# 4-IO.net
KiCad netlist of a schematic drawn in Altium Designer
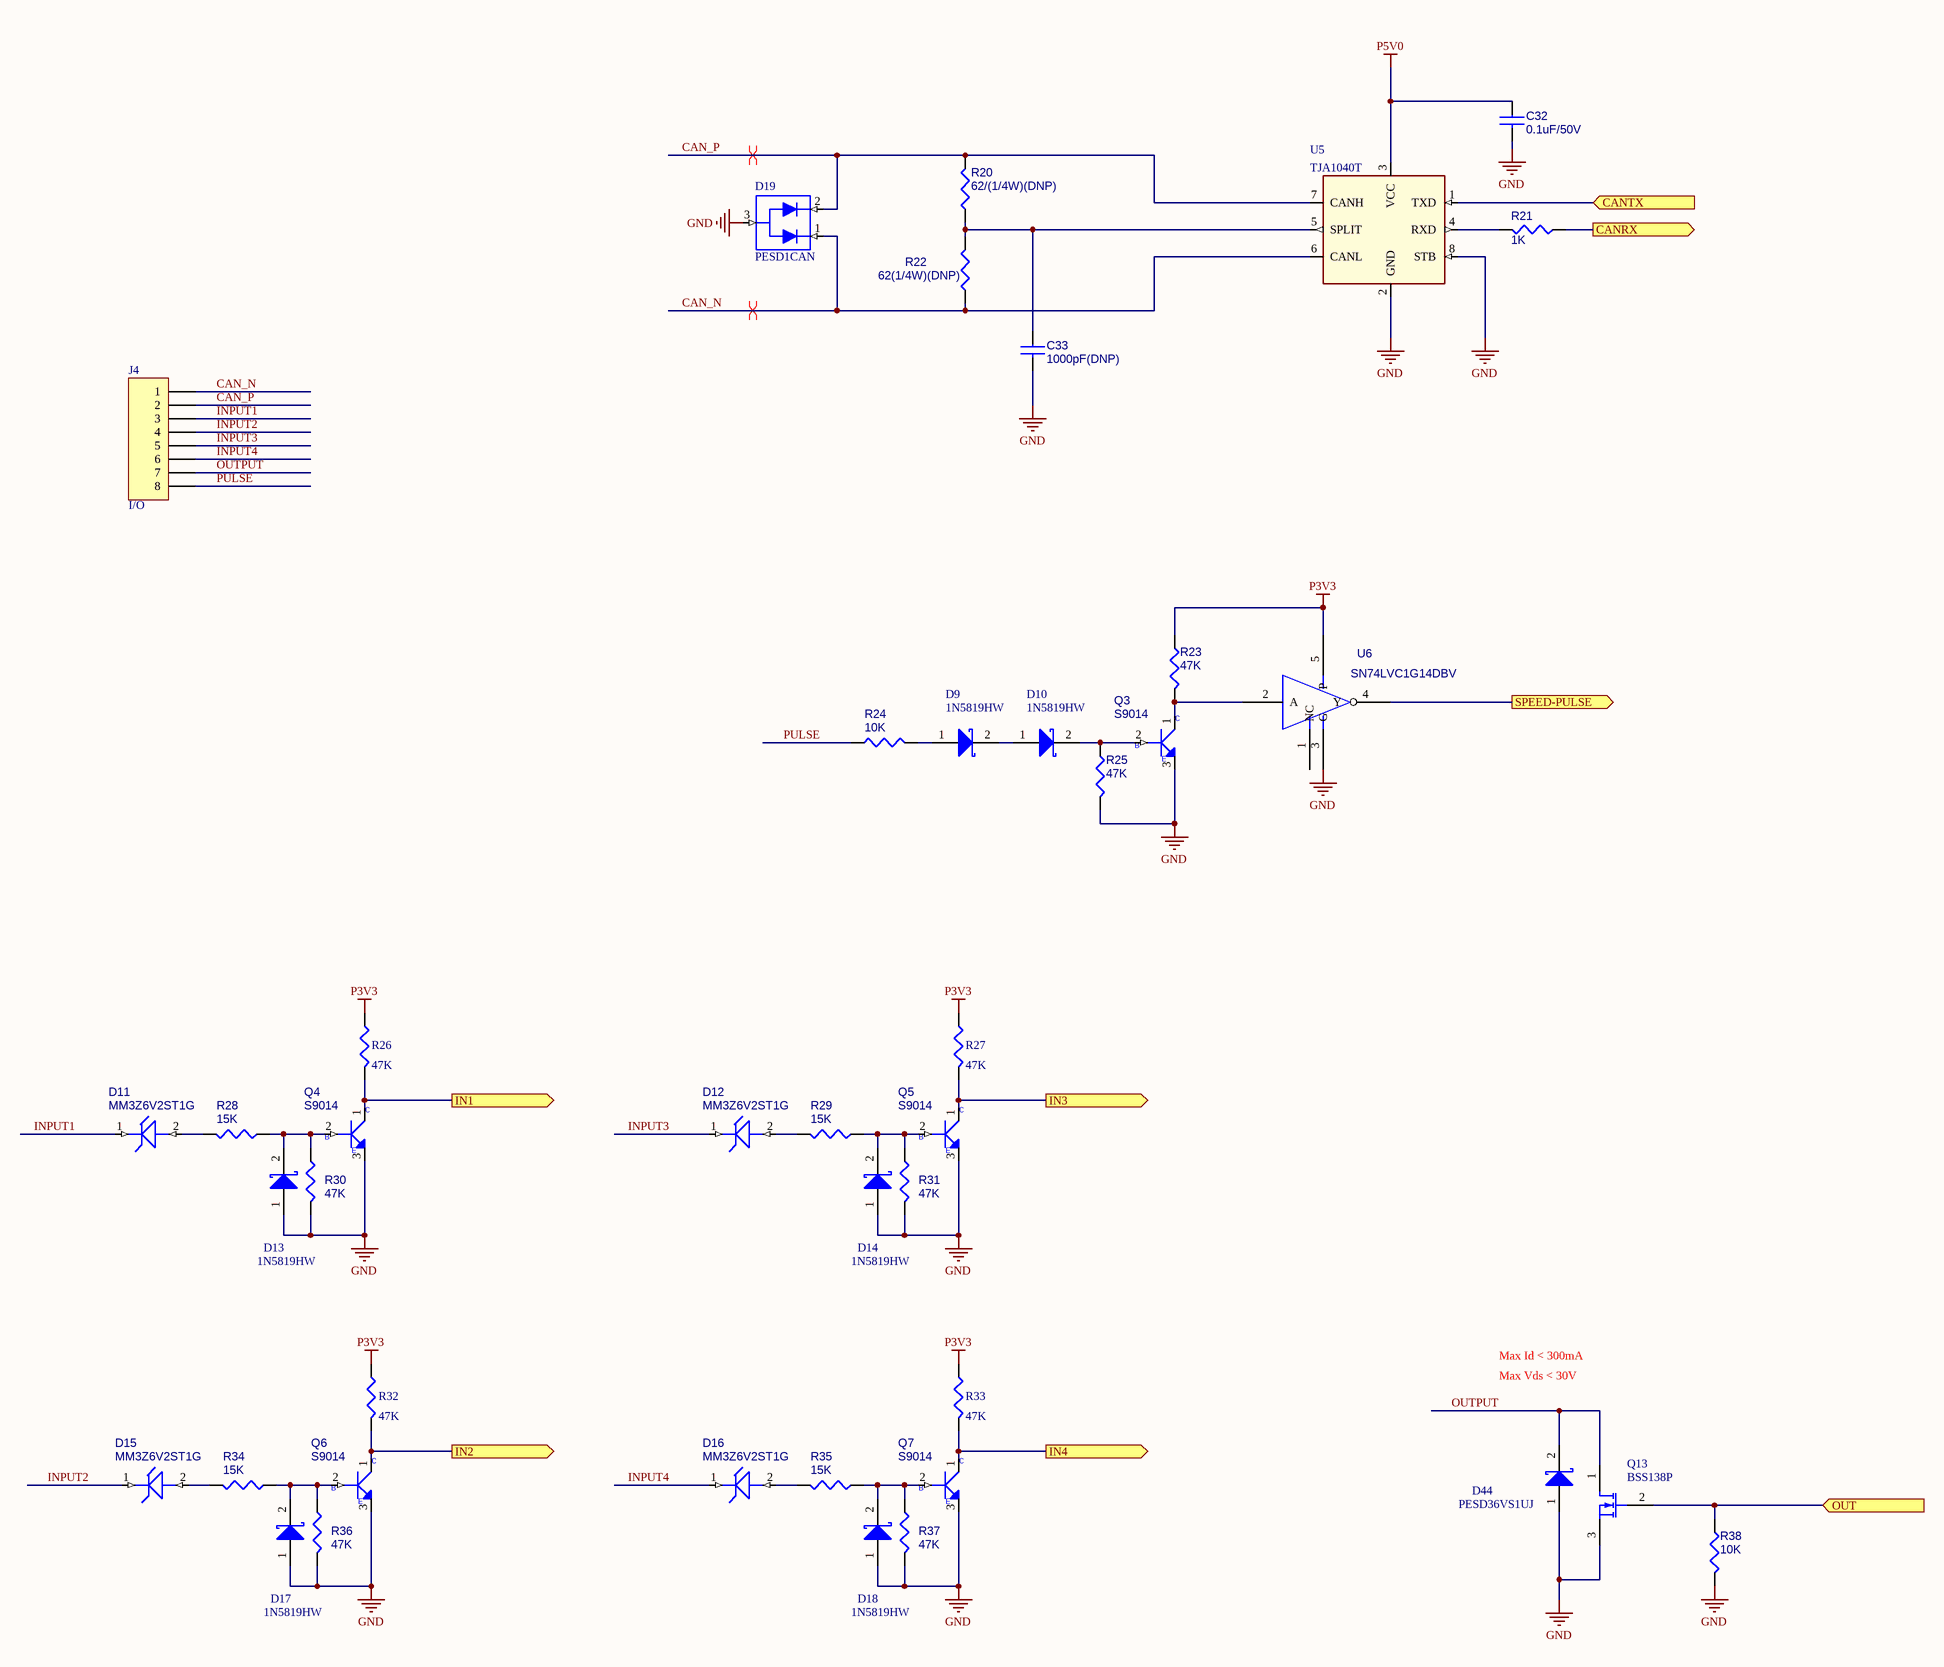
[diagram p0: 4-IO.SchDoc]

(export (version "E")
  (design (tool "Eeschema 10.0.6"))
  (components
    (comp (ref "C32") (value "0.1uF/50V") (libsource (lib "*") (part "P_CAP NP")))
    (comp (ref "C33") (value "1000pF(DNP)") (libsource (lib "*") (part "P_CAP NP")))
    (comp (ref "D9")
      (value "1N5819HW")
      (footprint "1N5819")
      (description "Schottky Rectifier")
      (libsource (lib "Miscellaneous Devices") (part "Diode 11DQ03"))
    )
    (comp (ref "D10")
      (value "1N5819HW")
      (footprint "1N5819")
      (description "Schottky Rectifier")
      (libsource (lib "Miscellaneous Devices") (part "Diode 11DQ03"))
    )
    (comp (ref "D11")
      (value "MM3Z6V2ST1G")
      (footprint "SOD323F")
      (libsource (lib "*") (part "MMGZ5231BPTLL34"))
    )
    (comp (ref "D12")
      (value "MM3Z6V2ST1G")
      (footprint "SOD323F")
      (libsource (lib "*") (part "MMGZ5231BPTLL34"))
    )
    (comp (ref "D13")
      (value "1N5819HW")
      (footprint "1N5819")
      (description "Schottky Rectifier")
      (libsource (lib "Miscellaneous Devices") (part "Diode 11DQ03"))
    )
    (comp (ref "D14")
      (value "1N5819HW")
      (footprint "1N5819")
      (description "Schottky Rectifier")
      (libsource (lib "Miscellaneous Devices") (part "Diode 11DQ03"))
    )
    (comp (ref "D15")
      (value "MM3Z6V2ST1G")
      (footprint "SOD323F")
      (libsource (lib "*") (part "MMGZ5231BPTLL34"))
    )
    (comp (ref "D16")
      (value "MM3Z6V2ST1G")
      (footprint "SOD323F")
      (libsource (lib "*") (part "MMGZ5231BPTLL34"))
    )
    (comp (ref "D17")
      (value "1N5819HW")
      (footprint "1N5819")
      (description "Schottky Rectifier")
      (libsource (lib "Miscellaneous Devices") (part "Diode 11DQ03"))
    )
    (comp (ref "D18")
      (value "1N5819HW")
      (footprint "1N5819")
      (description "Schottky Rectifier")
      (libsource (lib "Miscellaneous Devices") (part "Diode 11DQ03"))
    )
    (comp (ref "D19")
      (value "PESD1CAN")
      (footprint "PESD2CAN")
      (fields (field (name "PART NUMBER") "SCA00000J00"))
      (libsource (lib "Schlib") (part "PESD2CAN"))
    )
    (comp (ref "D44")
      (value "PESD36VS1UJ")
      (footprint "SOD323")
      (description "Schottky Rectifier")
      (libsource (lib "Miscellaneous Devices") (part "Diode 11DQ03"))
    )
    (comp (ref "J4")
      (value "I/O")
      (footprint "XH2.54-SMT-V-8P")
      (description "Header, 8-Pin")
      (fields (field (name "PUBLISHER") "Altium Limited"))
      (libsource (lib "Miscellaneous Connectors") (part "Header 8"))
    )
    (comp (ref "Q3")
      (value "S9014")
      (footprint "NPN")
      (fields (field (name "PART NUMBER") "SB039040000"))
      (libsource (lib "*") (part "MMBT3904_NL_SOT23-3"))
    )
    (comp (ref "Q4")
      (value "S9014")
      (footprint "NPN")
      (fields (field (name "PART NUMBER") "SB039040000"))
      (libsource (lib "*") (part "MMBT3904_NL_SOT23-3"))
    )
    (comp (ref "Q5")
      (value "S9014")
      (footprint "NPN")
      (fields (field (name "PART NUMBER") "SB039040000"))
      (libsource (lib "*") (part "MMBT3904_NL_SOT23-3"))
    )
    (comp (ref "Q6")
      (value "S9014")
      (footprint "NPN")
      (fields (field (name "PART NUMBER") "SB039040000"))
      (libsource (lib "*") (part "MMBT3904_NL_SOT23-3"))
    )
    (comp (ref "Q7")
      (value "S9014")
      (footprint "NPN")
      (fields (field (name "PART NUMBER") "SB039040000"))
      (libsource (lib "*") (part "MMBT3904_NL_SOT23-3"))
    )
    (comp (ref "Q13")
      (value "BSS138P")
      (footprint "NPN")
      (description "N-Channel MOSFET")
      (fields (field (name "PUBLISHER") "Altium Limited"))
      (libsource (lib "Miscellaneous Devices") (part "MOSFET-N"))
    )
    (comp (ref "R20") (value "62/(1/4W)(DNP)") (footprint "1206") (libsource (lib "*") (part "P_R")))
    (comp (ref "R21") (value "1K") (footprint "0402") (libsource (lib "*") (part "P_R")))
    (comp (ref "R22") (value "62(1/4W)(DNP)") (footprint "1206") (libsource (lib "*") (part "P_R")))
    (comp (ref "R23") (value "47K") (footprint "0402") (libsource (lib "*") (part "P_R")))
    (comp (ref "R24") (value "10K") (footprint "0402") (libsource (lib "*") (part "P_R")))
    (comp (ref "R25") (value "47K") (footprint "0402") (libsource (lib "*") (part "P_R")))
    (comp (ref "R26")
      (value "47K")
      (footprint "0402")
      (description "Resistor")
      (fields (field (name "PUBLISHER") "Altium Limited"))
      (libsource (lib "Miscellaneous Devices") (part "Res3"))
    )
    (comp (ref "R27")
      (value "47K")
      (footprint "0402")
      (description "Resistor")
      (fields (field (name "PUBLISHER") "Altium Limited"))
      (libsource (lib "Miscellaneous Devices") (part "Res3"))
    )
    (comp (ref "R28") (value "15K") (libsource (lib "*") (part "R")))
    (comp (ref "R29") (value "15K") (libsource (lib "*") (part "R")))
    (comp (ref "R30") (value "47K") (libsource (lib "*") (part "R")))
    (comp (ref "R31") (value "47K") (libsource (lib "*") (part "R")))
    (comp (ref "R32")
      (value "47K")
      (footprint "0402")
      (description "Resistor")
      (fields (field (name "PUBLISHER") "Altium Limited"))
      (libsource (lib "Miscellaneous Devices") (part "Res3"))
    )
    (comp (ref "R33")
      (value "47K")
      (footprint "0402")
      (description "Resistor")
      (fields (field (name "PUBLISHER") "Altium Limited"))
      (libsource (lib "Miscellaneous Devices") (part "Res3"))
    )
    (comp (ref "R34") (value "15K") (libsource (lib "*") (part "R")))
    (comp (ref "R35") (value "15K") (libsource (lib "*") (part "R")))
    (comp (ref "R36") (value "47K") (libsource (lib "*") (part "R")))
    (comp (ref "R37") (value "47K") (libsource (lib "*") (part "R")))
    (comp (ref "R38") (value "10K") (libsource (lib "*") (part "R")))
    (comp (ref "U5")
      (value "TJA1040T")
      (footprint "SO8")
      (description "IC XCVR CAN HS 5V SO8")
      (libsource (lib "*") (part "TJA1040T_SO_8P"))
    )
    (comp (ref "U6") (value "SN74LVC1G14DBV") (libsource (lib "*") (part "74LVC1G04GW_SOT353-5")))
  )
  (nets
    (net (code "1") (name "/CANRX") (class "Default")
      (node (ref "R21") (pin "2") (pinfunction "2_2") (pintype "passive"))
    )
    (net (code "2") (name "/CANTX") (class "Default")
      (node (ref "U5") (pin "1") (pinfunction "TXD_1") (pintype "input"))
    )
    (net (code "3") (name "/CAN_N") (class "Default")
      (node (ref "D19") (pin "1") (pinfunction "1_1") (pintype "input"))
      (node (ref "J4") (pin "1") (pinfunction "1_1") (pintype "passive"))
      (node (ref "R22") (pin "2") (pinfunction "2_2") (pintype "passive"))
      (node (ref "U5") (pin "6") (pinfunction "CANL_6") (pintype "bidirectional"))
    )
    (net (code "4") (name "/CAN_P") (class "Default")
      (node (ref "D19") (pin "2") (pinfunction "2_2") (pintype "input"))
      (node (ref "J4") (pin "2") (pinfunction "2_2") (pintype "passive"))
      (node (ref "R20") (pin "1") (pinfunction "1_1") (pintype "passive"))
      (node (ref "U5") (pin "7") (pinfunction "CANH_7") (pintype "bidirectional"))
    )
    (net (code "5") (name "/IN1") (class "Default")
      (node (ref "Q4") (pin "1") (pinfunction "COLLECTOR_1") (pintype "passive"))
      (node (ref "R26") (pin "2") (pinfunction "2_2") (pintype "passive"))
    )
    (net (code "6") (name "/IN2") (class "Default")
      (node (ref "Q6") (pin "1") (pinfunction "COLLECTOR_1") (pintype "passive"))
      (node (ref "R32") (pin "2") (pinfunction "2_2") (pintype "passive"))
    )
    (net (code "7") (name "/IN3") (class "Default")
      (node (ref "Q5") (pin "1") (pinfunction "COLLECTOR_1") (pintype "passive"))
      (node (ref "R27") (pin "2") (pinfunction "2_2") (pintype "passive"))
    )
    (net (code "8") (name "/IN4") (class "Default")
      (node (ref "Q7") (pin "1") (pinfunction "COLLECTOR_1") (pintype "passive"))
      (node (ref "R33") (pin "2") (pinfunction "2_2") (pintype "passive"))
    )
    (net (code "9") (name "/INPUT1") (class "Default")
      (node (ref "D11") (pin "1") (pinfunction "1_1") (pintype "input"))
      (node (ref "J4") (pin "3") (pinfunction "3_3") (pintype "passive"))
    )
    (net (code "10") (name "/INPUT2") (class "Default")
      (node (ref "D15") (pin "1") (pinfunction "1_1") (pintype "input"))
      (node (ref "J4") (pin "4") (pinfunction "4_4") (pintype "passive"))
    )
    (net (code "11") (name "/INPUT3") (class "Default")
      (node (ref "D12") (pin "1") (pinfunction "1_1") (pintype "input"))
      (node (ref "J4") (pin "5") (pinfunction "5_5") (pintype "passive"))
    )
    (net (code "12") (name "/INPUT4") (class "Default")
      (node (ref "D16") (pin "1") (pinfunction "1_1") (pintype "input"))
      (node (ref "J4") (pin "6") (pinfunction "6_6") (pintype "passive"))
    )
    (net (code "13") (name "/OUT") (class "Default")
      (node (ref "Q13") (pin "2") (pinfunction "G_2") (pintype "passive"))
      (node (ref "R38") (pin "1") (pinfunction "1_1") (pintype "passive"))
    )
    (net (code "14") (name "/OUTPUT") (class "Default")
      (node (ref "D44") (pin "2") (pinfunction "K_2") (pintype "passive"))
      (node (ref "J4") (pin "7") (pinfunction "7_7") (pintype "passive"))
      (node (ref "Q13") (pin "1") (pinfunction "D_1") (pintype "passive"))
    )
    (net (code "15") (name "/PULSE") (class "Default")
      (node (ref "J4") (pin "8") (pinfunction "8_8") (pintype "passive"))
      (node (ref "R24") (pin "2") (pinfunction "2_2") (pintype "passive"))
    )
    (net (code "16") (name "/SPEED-PULSE") (class "Default")
      (node (ref "U6") (pin "4") (pinfunction "Y_4") (pintype "passive"))
    )
    (net (code "17") (name "GND") (class "Default")
      (node (ref "C32") (pin "2") (pinfunction "2_2") (pintype "passive"))
      (node (ref "C33") (pin "2") (pinfunction "2_2") (pintype "passive"))
      (node (ref "D13") (pin "1") (pinfunction "A_1") (pintype "passive"))
      (node (ref "D14") (pin "1") (pinfunction "A_1") (pintype "passive"))
      (node (ref "D17") (pin "1") (pinfunction "A_1") (pintype "passive"))
      (node (ref "D18") (pin "1") (pinfunction "A_1") (pintype "passive"))
      (node (ref "D19") (pin "3") (pinfunction "3_3") (pintype "input"))
      (node (ref "D44") (pin "1") (pinfunction "A_1") (pintype "passive"))
      (node (ref "Q13") (pin "3") (pinfunction "S_3") (pintype "passive"))
      (node (ref "Q3") (pin "3") (pinfunction "EMITTER_3") (pintype "passive"))
      (node (ref "Q4") (pin "3") (pinfunction "EMITTER_3") (pintype "passive"))
      (node (ref "Q5") (pin "3") (pinfunction "EMITTER_3") (pintype "passive"))
      (node (ref "Q6") (pin "3") (pinfunction "EMITTER_3") (pintype "passive"))
      (node (ref "Q7") (pin "3") (pinfunction "EMITTER_3") (pintype "passive"))
      (node (ref "R25") (pin "1") (pinfunction "1_1") (pintype "passive"))
      (node (ref "R30") (pin "2") (pinfunction "2_2") (pintype "passive"))
      (node (ref "R31") (pin "2") (pinfunction "2_2") (pintype "passive"))
      (node (ref "R36") (pin "2") (pinfunction "2_2") (pintype "passive"))
      (node (ref "R37") (pin "2") (pinfunction "2_2") (pintype "passive"))
      (node (ref "R38") (pin "2") (pinfunction "2_2") (pintype "passive"))
      (node (ref "U5") (pin "2") (pinfunction "GND_2") (pintype "power_in"))
      (node (ref "U5") (pin "8") (pinfunction "STB_8") (pintype "input"))
      (node (ref "U6") (pin "3") (pinfunction "G_3") (pintype "passive"))
    )
    (net (code "18") (name "Net-(D9-A)") (class "Default")
      (node (ref "D9") (pin "1") (pinfunction "A_1") (pintype "passive"))
      (node (ref "R24") (pin "1") (pinfunction "1_1") (pintype "passive"))
    )
    (net (code "19") (name "Net-(D10-A)") (class "Default")
      (node (ref "D10") (pin "1") (pinfunction "A_1") (pintype "passive"))
      (node (ref "D9") (pin "2") (pinfunction "K_2") (pintype "passive"))
    )
    (net (code "20") (name "Net-(D10-K)") (class "Default")
      (node (ref "D10") (pin "2") (pinfunction "K_2") (pintype "passive"))
      (node (ref "Q3") (pin "2") (pinfunction "BASE_2") (pintype "input"))
      (node (ref "R25") (pin "2") (pinfunction "2_2") (pintype "passive"))
    )
    (net (code "21") (name "Net-(D11-Pad2)") (class "Default")
      (node (ref "D11") (pin "2") (pinfunction "2_2") (pintype "input"))
      (node (ref "R28") (pin "2") (pinfunction "2_2") (pintype "passive"))
    )
    (net (code "22") (name "Net-(D12-Pad2)") (class "Default")
      (node (ref "D12") (pin "2") (pinfunction "2_2") (pintype "input"))
      (node (ref "R29") (pin "2") (pinfunction "2_2") (pintype "passive"))
    )
    (net (code "23") (name "Net-(D13-K)") (class "Default")
      (node (ref "D13") (pin "2") (pinfunction "K_2") (pintype "passive"))
      (node (ref "Q4") (pin "2") (pinfunction "BASE_2") (pintype "input"))
      (node (ref "R28") (pin "1") (pinfunction "1_1") (pintype "passive"))
      (node (ref "R30") (pin "1") (pinfunction "1_1") (pintype "passive"))
    )
    (net (code "24") (name "Net-(D14-K)") (class "Default")
      (node (ref "D14") (pin "2") (pinfunction "K_2") (pintype "passive"))
      (node (ref "Q5") (pin "2") (pinfunction "BASE_2") (pintype "input"))
      (node (ref "R29") (pin "1") (pinfunction "1_1") (pintype "passive"))
      (node (ref "R31") (pin "1") (pinfunction "1_1") (pintype "passive"))
    )
    (net (code "25") (name "Net-(D15-Pad2)") (class "Default")
      (node (ref "D15") (pin "2") (pinfunction "2_2") (pintype "input"))
      (node (ref "R34") (pin "2") (pinfunction "2_2") (pintype "passive"))
    )
    (net (code "26") (name "Net-(D16-Pad2)") (class "Default")
      (node (ref "D16") (pin "2") (pinfunction "2_2") (pintype "input"))
      (node (ref "R35") (pin "2") (pinfunction "2_2") (pintype "passive"))
    )
    (net (code "27") (name "Net-(D17-K)") (class "Default")
      (node (ref "D17") (pin "2") (pinfunction "K_2") (pintype "passive"))
      (node (ref "Q6") (pin "2") (pinfunction "BASE_2") (pintype "input"))
      (node (ref "R34") (pin "1") (pinfunction "1_1") (pintype "passive"))
      (node (ref "R36") (pin "1") (pinfunction "1_1") (pintype "passive"))
    )
    (net (code "28") (name "Net-(D18-K)") (class "Default")
      (node (ref "D18") (pin "2") (pinfunction "K_2") (pintype "passive"))
      (node (ref "Q7") (pin "2") (pinfunction "BASE_2") (pintype "input"))
      (node (ref "R35") (pin "1") (pinfunction "1_1") (pintype "passive"))
      (node (ref "R37") (pin "1") (pinfunction "1_1") (pintype "passive"))
    )
    (net (code "29") (name "Net-(Q3-COLLECTOR)") (class "Default")
      (node (ref "Q3") (pin "1") (pinfunction "COLLECTOR_1") (pintype "passive"))
      (node (ref "R23") (pin "1") (pinfunction "1_1") (pintype "passive"))
      (node (ref "U6") (pin "2") (pinfunction "A_2") (pintype "passive"))
    )
    (net (code "30") (name "Net-(U5-RXD)") (class "Default")
      (node (ref "R21") (pin "1") (pinfunction "1_1") (pintype "passive"))
      (node (ref "U5") (pin "4") (pinfunction "RXD_4") (pintype "output"))
    )
    (net (code "31") (name "Net-(U5-SPLIT)") (class "Default")
      (node (ref "C33") (pin "1") (pinfunction "1_1") (pintype "passive"))
      (node (ref "R20") (pin "2") (pinfunction "2_2") (pintype "passive"))
      (node (ref "R22") (pin "1") (pinfunction "1_1") (pintype "passive"))
      (node (ref "U5") (pin "5") (pinfunction "SPLIT_5") (pintype "output"))
    )
    (net (code "32") (name "P3V3") (class "Default")
      (node (ref "R23") (pin "2") (pinfunction "2_2") (pintype "passive"))
      (node (ref "R26") (pin "1") (pinfunction "1_1") (pintype "passive"))
      (node (ref "R27") (pin "1") (pinfunction "1_1") (pintype "passive"))
      (node (ref "R32") (pin "1") (pinfunction "1_1") (pintype "passive"))
      (node (ref "R33") (pin "1") (pinfunction "1_1") (pintype "passive"))
      (node (ref "U6") (pin "5") (pinfunction "P_5") (pintype "passive"))
    )
    (net (code "33") (name "P5V0") (class "Default")
      (node (ref "C32") (pin "1") (pinfunction "1_1") (pintype "passive"))
      (node (ref "U5") (pin "3") (pinfunction "VCC_3") (pintype "power_in"))
    )
    (net (code "34") (name "unconnected-(U6-NC-Pad1)") (class "Default")
      (node (ref "U6") (pin "1") (pinfunction "NC_1") (pintype "passive"))
    )
  )
)
